# SCH_TouchScreenMotorController_2025-12-2.net
KiCad netlist of a schematic drawn in EasyEDA
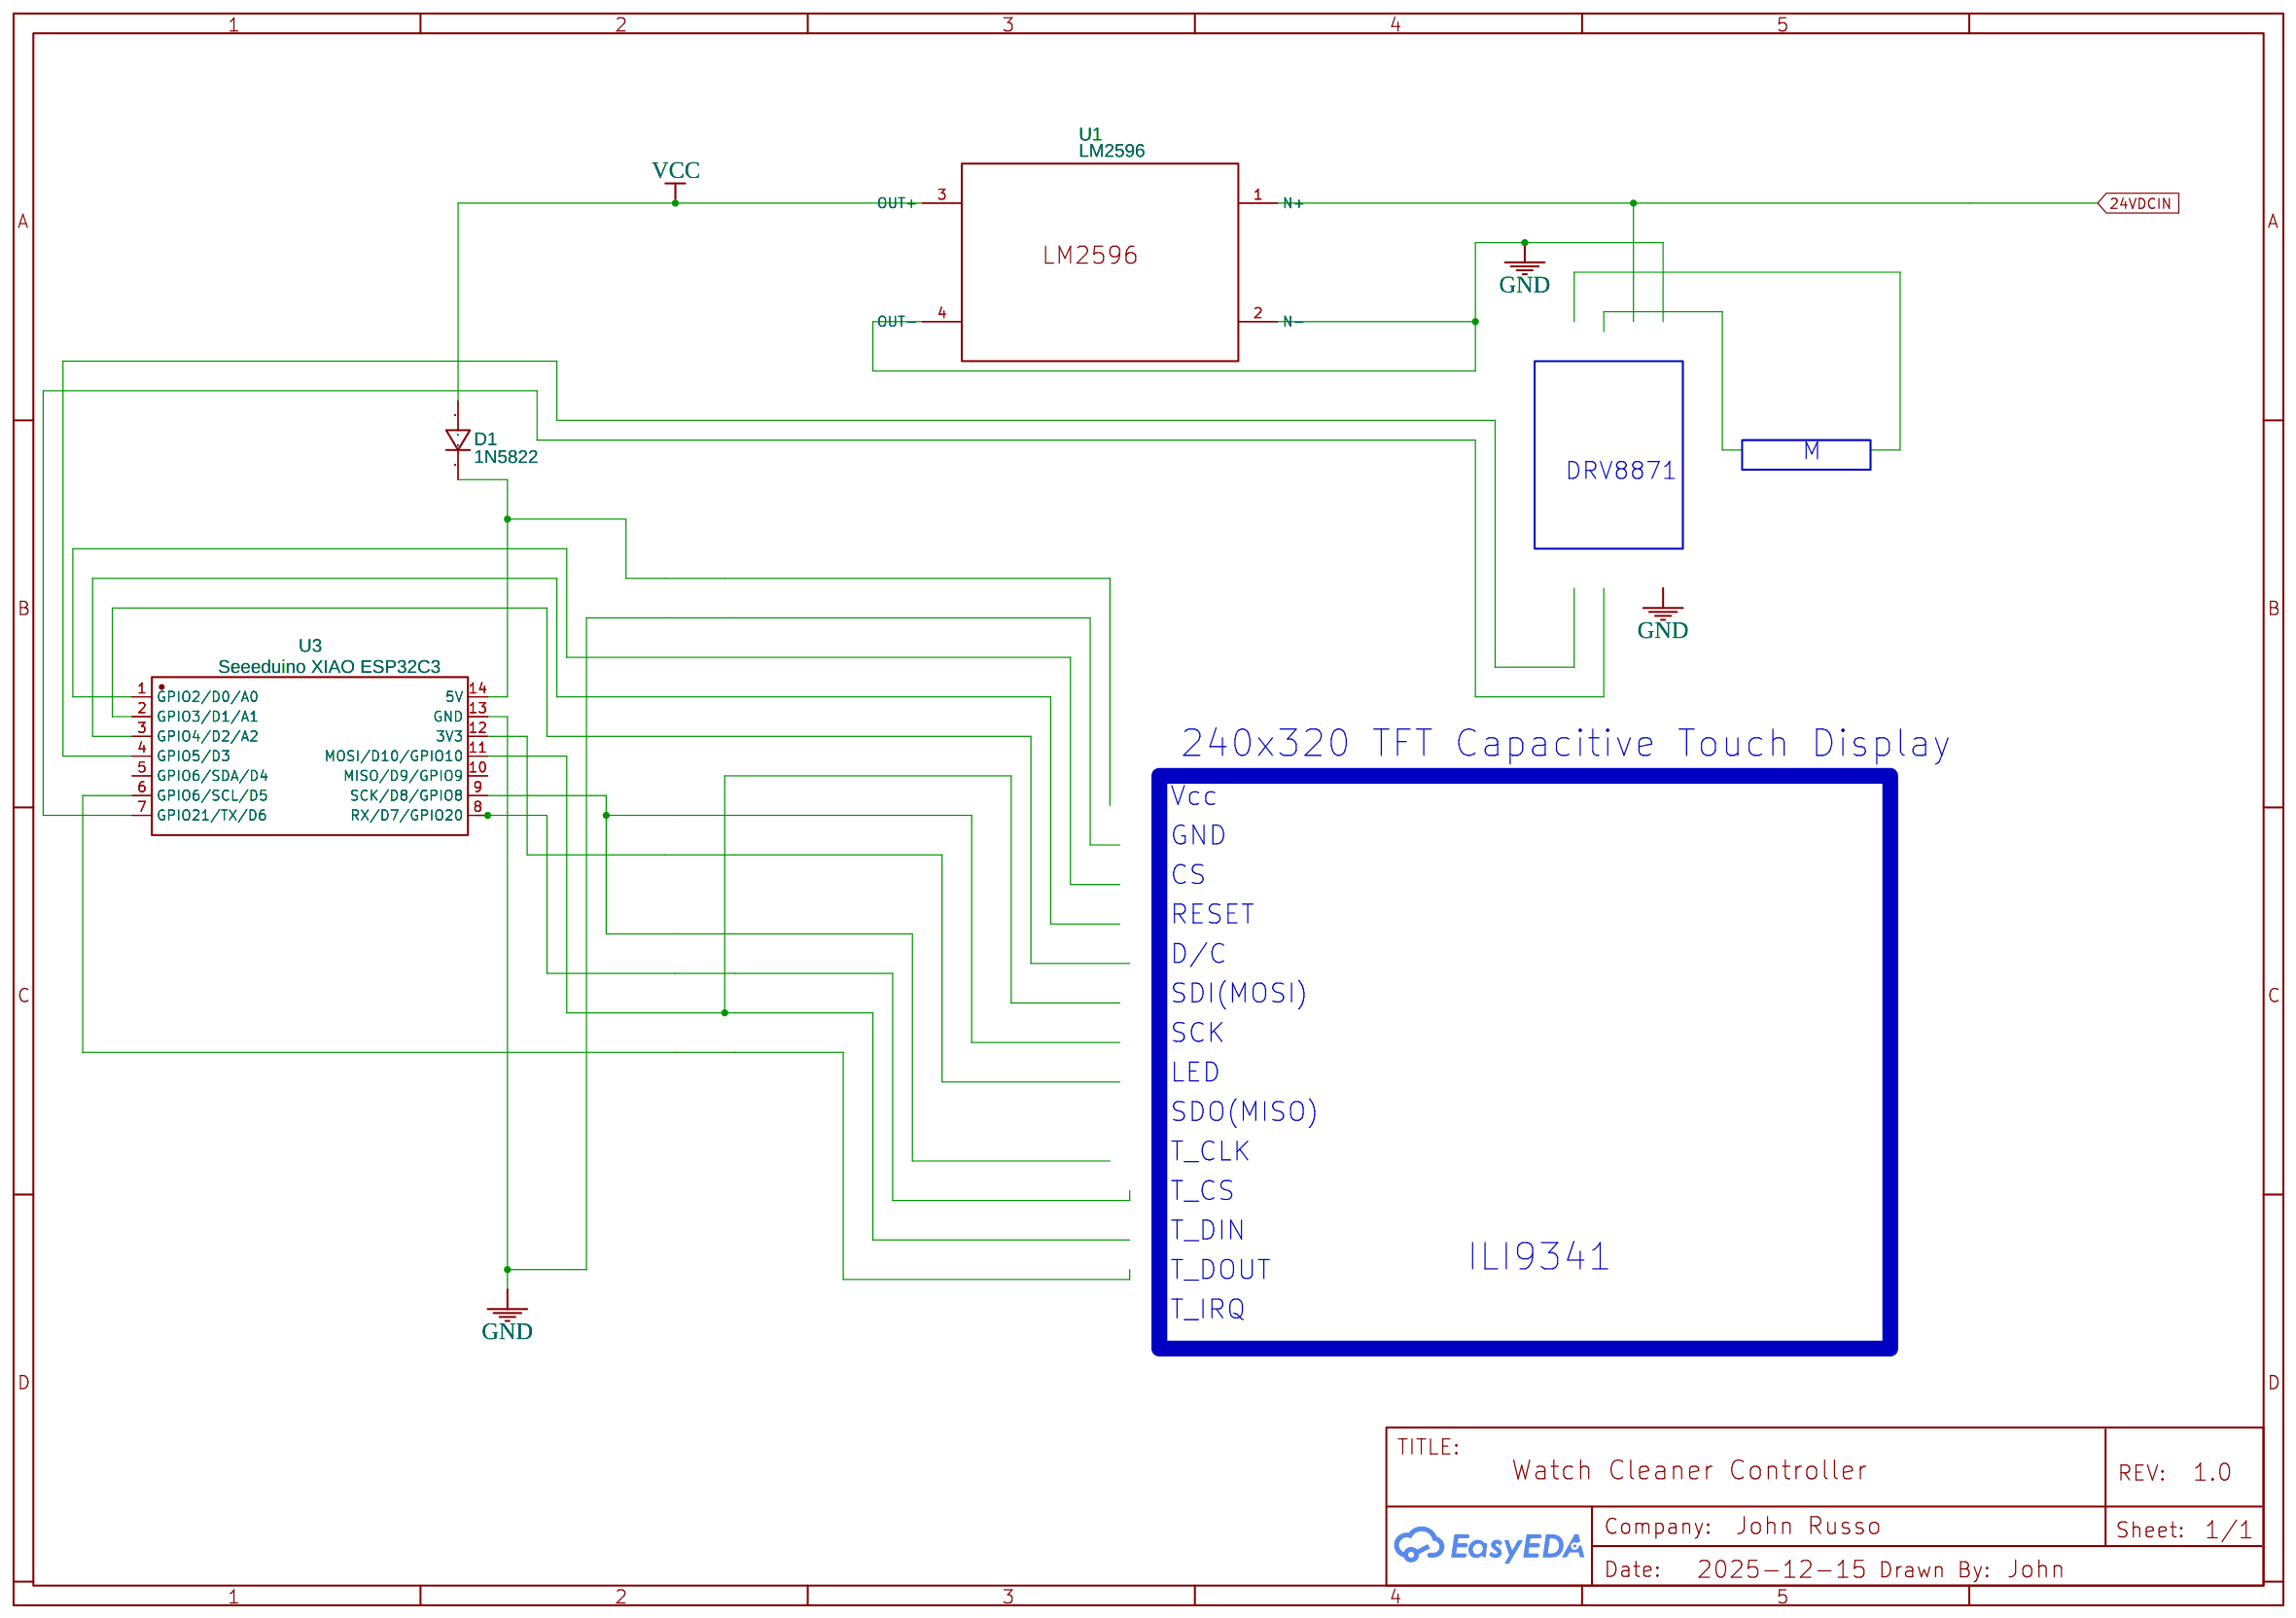
[diagram p0: schematic sheet]

(export (version "E")
  (design (tool "Eeschema 10.0.6"))
  (components
    (comp (ref "D1")
      (value "1N5822")
      (fields (field (name "Manufacturer Part") "1N4007W") (field (name "Manufacturer") "BLUE ROCKET"))
      (libsource (lib "") (part "1N4007W"))
    )
    (comp (ref "U1") (value "LM2596") (libsource (lib "") (part "LM2596")))
    (comp (ref "U3") (value "Seeeduino XIAO ESP32C3") (libsource (lib "") (part "Seeeduino XIAO")))
  )
  (nets
    (net (code "2") (name "GND") (class "Default")
      (node (ref "U3") (pin "13") (pinfunction "GND_13") (pintype "unspecified"))
    )
    (net (code "3") (name "Net-(U3-5V)") (class "Default")
      (node (ref "D1") (pin "1") (pinfunction "1_1") (pintype "unspecified"))
      (node (ref "U3") (pin "14") (pinfunction "5V_14") (pintype "unspecified"))
    )
    (net (code "4") (name "VCC") (class "Default")
      (node (ref "D1") (pin "2") (pinfunction "2_2") (pintype "unspecified"))
    )
    (net (code "5") (name "unconnected-(U1-N+-Pad1)") (class "Default")
      (node (ref "U1") (pin "1") (pinfunction "N+_1") (pintype "unspecified"))
    )
    (net (code "6") (name "unconnected-(U1-N--Pad2)") (class "Default")
      (node (ref "U1") (pin "2") (pinfunction "N-_2") (pintype "unspecified"))
    )
    (net (code "7") (name "unconnected-(U1-OUT+-Pad3)") (class "Default")
      (node (ref "U1") (pin "3") (pinfunction "OUT+_3") (pintype "unspecified"))
    )
    (net (code "8") (name "unconnected-(U1-OUT--Pad4)") (class "Default")
      (node (ref "U1") (pin "4") (pinfunction "OUT-_4") (pintype "unspecified"))
    )
    (net (code "9") (name "unconnected-(U3-3V3-Pad12)") (class "Default")
      (node (ref "U3") (pin "12") (pinfunction "3V3_12") (pintype "unspecified"))
    )
    (net (code "10") (name "unconnected-(U3-GPIO2{slash}D0{slash}A0-Pad1)") (class "Default")
      (node (ref "U3") (pin "1") (pinfunction "GPIO2/D0/A0_1") (pintype "unspecified"))
    )
    (net (code "11") (name "unconnected-(U3-GPIO3{slash}D1{slash}A1-Pad2)") (class "Default")
      (node (ref "U3") (pin "2") (pinfunction "GPIO3/D1/A1_2") (pintype "unspecified"))
    )
    (net (code "12") (name "unconnected-(U3-GPIO4{slash}D2{slash}A2-Pad3)") (class "Default")
      (node (ref "U3") (pin "3") (pinfunction "GPIO4/D2/A2_3") (pintype "unspecified"))
    )
    (net (code "13") (name "unconnected-(U3-GPIO5{slash}D3-Pad4)") (class "Default")
      (node (ref "U3") (pin "4") (pinfunction "GPIO5/D3_4") (pintype "unspecified"))
    )
    (net (code "14") (name "unconnected-(U3-GPIO6{slash}SCL{slash}D5-Pad6)") (class "Default")
      (node (ref "U3") (pin "6") (pinfunction "GPIO6/SCL/D5_6") (pintype "unspecified"))
    )
    (net (code "15") (name "unconnected-(U3-GPIO6{slash}SDA{slash}D4-Pad5)") (class "Default")
      (node (ref "U3") (pin "5") (pinfunction "GPIO6/SDA/D4_5") (pintype "unspecified"))
    )
    (net (code "16") (name "unconnected-(U3-GPIO21{slash}TX{slash}D6-Pad7)") (class "Default")
      (node (ref "U3") (pin "7") (pinfunction "GPIO21/TX/D6_7") (pintype "unspecified"))
    )
    (net (code "17") (name "unconnected-(U3-MISO{slash}D9{slash}GPIO9-Pad10)") (class "Default")
      (node (ref "U3") (pin "10") (pinfunction "MISO/D9/GPIO9_10") (pintype "unspecified"))
    )
    (net (code "18") (name "unconnected-(U3-MOSI{slash}D10{slash}GPIO10-Pad11)") (class "Default")
      (node (ref "U3") (pin "11") (pinfunction "MOSI/D10/GPIO10_11") (pintype "unspecified"))
    )
    (net (code "19") (name "unconnected-(U3-RX{slash}D7{slash}GPIO20-Pad8)") (class "Default")
      (node (ref "U3") (pin "8") (pinfunction "RX/D7/GPIO20_8") (pintype "unspecified"))
    )
    (net (code "20") (name "unconnected-(U3-SCK{slash}D8{slash}GPIO8-Pad9)") (class "Default")
      (node (ref "U3") (pin "9") (pinfunction "SCK/D8/GPIO8_9") (pintype "unspecified"))
    )
  )
)
